# Addon-mapleCUx_Raspi-3V3-UART-CC2530-V01.net
KiCad netlist of a schematic drawn in EAGLE
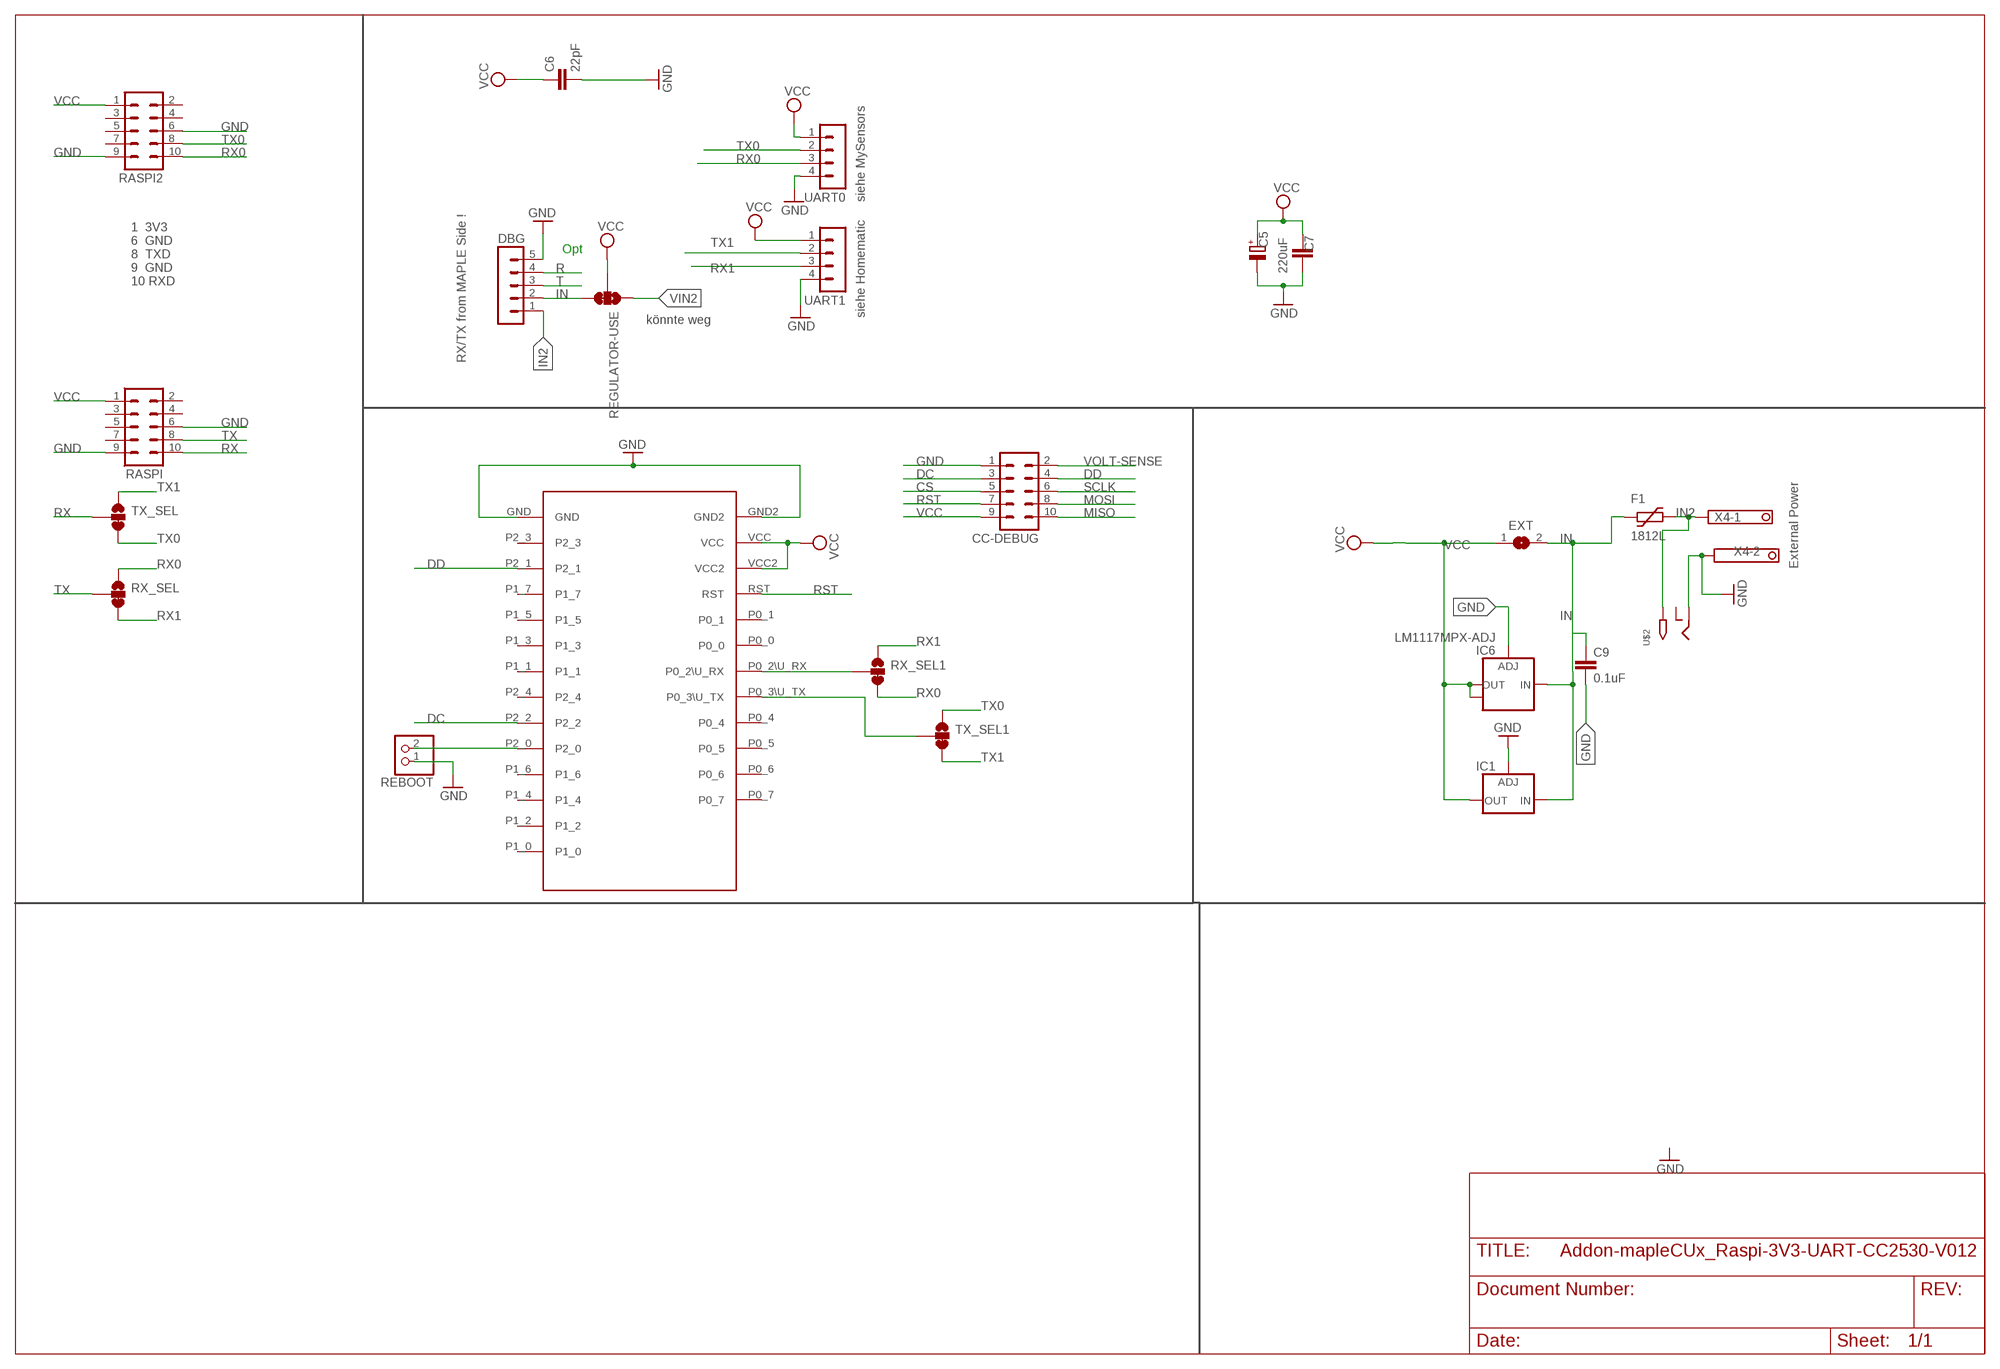
[diagram p0: schematic, sheet 1]

(export (version "E")
  (design (tool "Eeschema 10.0.6"))
  (components
    (comp (ref "C5")
      (value "220uF")
      (footprint "eagle-import:E5-8,5")
      (libsource (lib "eagle-import") (part "CPOL-EUE5-8.5"))
    )
    (comp (ref "C6")
      (value "22pF")
      (footprint "eagle-import:C0805")
      (libsource (lib "eagle-import") (part "C-EUC0805"))
    )
    (comp (ref "C7")
      (value "C-EUC1812")
      (footprint "eagle-import:C1812")
      (libsource (lib "eagle-import") (part "C-EUC1812"))
    )
    (comp (ref "C9")
      (value "0.1uF")
      (footprint "eagle-import:C1206")
      (libsource (lib "eagle-import") (part "C-EUC1206"))
    )
    (comp (ref "CC-DEBUG")
      (value "MA05-2")
      (footprint "eagle-import:MA05-2")
      (libsource (lib "eagle-import") (part "MA05-2"))
    )
    (comp (ref "DBG")
      (value "MA05-1")
      (footprint "eagle-import:MA05-1")
      (libsource (lib "eagle-import") (part "MA05-1"))
    )
    (comp (ref "EXT") (value "SJ") (footprint "eagle-import:SJ") (libsource (lib "eagle-import") (part "SJ")))
    (comp (ref "F1")
      (value "1812L")
      (footprint "eagle-import:1812L")
      (libsource (lib "eagle-import") (part "1812L"))
    )
    (comp (ref "IC1")
      (value "LD117ADT50TR")
      (footprint "eagle-import:DPACK")
      (libsource (lib "eagle-import") (part "LD117A?DT50TR"))
    )
    (comp (ref "IC6")
      (value "LM1117MPX-ADJ")
      (footprint "eagle-import:SOT223")
      (libsource (lib "eagle-import") (part "LM1117MPX-ADJ"))
    )
    (comp (ref "RASPI")
      (value "MA05-2")
      (footprint "eagle-import:MA05-2")
      (libsource (lib "eagle-import") (part "MA05-2"))
    )
    (comp (ref "RASPI2")
      (value "MA05-2")
      (footprint "eagle-import:MA05-2")
      (libsource (lib "eagle-import") (part "MA05-2"))
    )
    (comp (ref "REBOOT")
      (value "PINHD-1X2")
      (footprint "eagle-import:1X02")
      (libsource (lib "eagle-import") (part "PINHD-1X2"))
    )
    (comp (ref "REGULATOR-USE")
      (value "JUMPER-SMT_3_1-NC_TRACE_SILK")
      (footprint "eagle-import:SMT-JUMPER_3_1-NC_TRACE_SILK")
      (libsource (lib "eagle-import") (part "JUMPER-SMT_3_1-NC_TRACE_SILK"))
    )
    (comp (ref "RX_SEL")
      (value "JUMPER-SMT_3_1-NC_TRACE_SILK")
      (footprint "eagle-import:SMT-JUMPER_3_1-NC_TRACE_SILK")
      (libsource (lib "eagle-import") (part "JUMPER-SMT_3_1-NC_TRACE_SILK"))
    )
    (comp (ref "RX_SEL1")
      (value "JUMPER-SMT_3_1-NC_TRACE_SILK")
      (footprint "eagle-import:SMT-JUMPER_3_1-NC_TRACE_SILK")
      (libsource (lib "eagle-import") (part "JUMPER-SMT_3_1-NC_TRACE_SILK"))
    )
    (comp (ref "TX_SEL")
      (value "JUMPER-SMT_3_1-NC_TRACE_SILK")
      (footprint "eagle-import:SMT-JUMPER_3_1-NC_TRACE_SILK")
      (libsource (lib "eagle-import") (part "JUMPER-SMT_3_1-NC_TRACE_SILK"))
    )
    (comp (ref "TX_SEL1")
      (value "JUMPER-SMT_3_1-NC_TRACE_SILK")
      (footprint "eagle-import:SMT-JUMPER_3_1-NC_TRACE_SILK")
      (libsource (lib "eagle-import") (part "JUMPER-SMT_3_1-NC_TRACE_SILK"))
    )
    (comp (ref "U$2")
      (value "2.1MMJACKTHM")
      (footprint "eagle-import:PJ-102A")
      (libsource (lib "eagle-import") (part "2.1MMJACKTHM"))
    )
    (comp (ref "U$3")
      (value "CC2530_MODULE")
      (footprint "eagle-import:CC2530_DIL")
      (libsource (lib "eagle-import") (part "CC2530_MODULE"))
    )
    (comp (ref "UART0")
      (value "MA04-1")
      (footprint "eagle-import:MA04-1")
      (libsource (lib "eagle-import") (part "MA04-1"))
    )
    (comp (ref "UART1")
      (value "MA04-1")
      (footprint "eagle-import:MA04-1")
      (libsource (lib "eagle-import") (part "MA04-1"))
    )
    (comp (ref "X4")
      (value "1751248")
      (footprint "eagle-import:1751248")
      (libsource (lib "eagle-import") (part "1751248"))
    )
  )
  (nets
    (net (code "1") (name "/CS") (class "Default")
      (node (ref "CC-DEBUG") (pin "5") (pinfunction "5_5") (pintype "passive"))
    )
    (net (code "2") (name "/DC") (class "Default")
      (node (ref "CC-DEBUG") (pin "3") (pinfunction "3_3") (pintype "passive"))
      (node (ref "U$3") (pin "P2_2") (pinfunction "P2_2_P2_2") (pintype "bidirectional"))
    )
    (net (code "3") (name "/DD") (class "Default")
      (node (ref "CC-DEBUG") (pin "4") (pinfunction "4_4") (pintype "passive"))
      (node (ref "U$3") (pin "P2_1") (pinfunction "P2_1_P2_1") (pintype "bidirectional"))
    )
    (net (code "4") (name "/IN") (class "Default")
      (node (ref "C9") (pin "1") (pinfunction "1_1") (pintype "passive"))
      (node (ref "DBG") (pin "2") (pinfunction "2_2") (pintype "passive"))
      (node (ref "EXT") (pin "2") (pinfunction "2_2") (pintype "passive"))
      (node (ref "F1") (pin "P$1") (pinfunction "1_P$1") (pintype "passive"))
      (node (ref "IC1") (pin "3") (pinfunction "IN_3") (pintype "input"))
      (node (ref "IC6") (pin "3") (pinfunction "IN_3") (pintype "input"))
      (node (ref "REGULATOR-USE") (pin "3") (pinfunction "3_3") (pintype "passive"))
    )
    (net (code "5") (name "/MISO") (class "Default")
      (node (ref "CC-DEBUG") (pin "10") (pinfunction "10_10") (pintype "passive"))
    )
    (net (code "6") (name "/MOSI") (class "Default")
      (node (ref "CC-DEBUG") (pin "8") (pinfunction "8_8") (pintype "passive"))
    )
    (net (code "7") (name "/R") (class "Default")
      (node (ref "DBG") (pin "4") (pinfunction "4_4") (pintype "passive"))
    )
    (net (code "8") (name "/RST") (class "Default")
      (node (ref "CC-DEBUG") (pin "7") (pinfunction "7_7") (pintype "passive"))
      (node (ref "U$3") (pin "RST") (pinfunction "RST_RST") (pintype "bidirectional"))
    )
    (net (code "9") (name "/RX") (class "Default")
      (node (ref "RASPI") (pin "10") (pinfunction "10_10") (pintype "passive"))
      (node (ref "TX_SEL") (pin "2") (pinfunction "2_2") (pintype "passive"))
    )
    (net (code "10") (name "/RX0") (class "Default")
      (node (ref "RASPI2") (pin "10") (pinfunction "10_10") (pintype "passive"))
      (node (ref "RX_SEL") (pin "1") (pinfunction "1_1") (pintype "passive"))
      (node (ref "RX_SEL1") (pin "3") (pinfunction "3_3") (pintype "passive"))
      (node (ref "UART0") (pin "3") (pinfunction "3_3") (pintype "passive"))
    )
    (net (code "11") (name "/RX1") (class "Default")
      (node (ref "RX_SEL") (pin "3") (pinfunction "3_3") (pintype "passive"))
      (node (ref "RX_SEL1") (pin "1") (pinfunction "1_1") (pintype "passive"))
      (node (ref "UART1") (pin "3") (pinfunction "3_3") (pintype "passive"))
    )
    (net (code "12") (name "/SCLK") (class "Default")
      (node (ref "CC-DEBUG") (pin "6") (pinfunction "6_6") (pintype "passive"))
    )
    (net (code "13") (name "/T") (class "Default")
      (node (ref "DBG") (pin "3") (pinfunction "3_3") (pintype "passive"))
    )
    (net (code "14") (name "/TX") (class "Default")
      (node (ref "RASPI") (pin "8") (pinfunction "8_8") (pintype "passive"))
      (node (ref "RX_SEL") (pin "2") (pinfunction "2_2") (pintype "passive"))
    )
    (net (code "15") (name "/TX0") (class "Default")
      (node (ref "RASPI2") (pin "8") (pinfunction "8_8") (pintype "passive"))
      (node (ref "TX_SEL") (pin "3") (pinfunction "3_3") (pintype "passive"))
      (node (ref "TX_SEL1") (pin "1") (pinfunction "1_1") (pintype "passive"))
      (node (ref "UART0") (pin "2") (pinfunction "2_2") (pintype "passive"))
    )
    (net (code "16") (name "/TX1") (class "Default")
      (node (ref "TX_SEL") (pin "1") (pinfunction "1_1") (pintype "passive"))
      (node (ref "TX_SEL1") (pin "3") (pinfunction "3_3") (pintype "passive"))
      (node (ref "UART1") (pin "2") (pinfunction "2_2") (pintype "passive"))
    )
    (net (code "17") (name "/VOLT-SENSE") (class "Default")
      (node (ref "CC-DEBUG") (pin "2") (pinfunction "2_2") (pintype "passive"))
    )
    (net (code "18") (name "GND") (class "Default")
      (node (ref "C5") (pin "-") (pinfunction "-_-") (pintype "passive"))
      (node (ref "C6") (pin "2") (pinfunction "2_2") (pintype "passive"))
      (node (ref "C7") (pin "1") (pinfunction "1_1") (pintype "passive"))
      (node (ref "C9") (pin "2") (pinfunction "2_2") (pintype "passive"))
      (node (ref "CC-DEBUG") (pin "1") (pinfunction "1_1") (pintype "passive"))
      (node (ref "DBG") (pin "5") (pinfunction "5_5") (pintype "passive"))
      (node (ref "IC1") (pin "1") (pinfunction "ADJ_1") (pintype "input"))
      (node (ref "IC6") (pin "1") (pinfunction "ADJ_1") (pintype "input"))
      (node (ref "RASPI") (pin "6") (pinfunction "6_6") (pintype "passive"))
      (node (ref "RASPI") (pin "9") (pinfunction "9_9") (pintype "passive"))
      (node (ref "RASPI2") (pin "6") (pinfunction "6_6") (pintype "passive"))
      (node (ref "RASPI2") (pin "9") (pinfunction "9_9") (pintype "passive"))
      (node (ref "REBOOT") (pin "1") (pinfunction "1_1") (pintype "passive"))
      (node (ref "U$2") (pin "RING") (pinfunction "RING_RING") (pintype "bidirectional"))
      (node (ref "U$3") (pin "GND") (pinfunction "GND_GND") (pintype "bidirectional"))
      (node (ref "U$3") (pin "GND2") (pinfunction "GND2_GND2") (pintype "bidirectional"))
      (node (ref "UART0") (pin "4") (pinfunction "4_4") (pintype "passive"))
      (node (ref "UART1") (pin "4") (pinfunction "4_4") (pintype "passive"))
      (node (ref "X4") (pin "2") (pinfunction "K_2") (pintype "passive"))
    )
    (net (code "19") (name "IN2") (class "Default")
      (node (ref "DBG") (pin "1") (pinfunction "1_1") (pintype "passive"))
      (node (ref "F1") (pin "P$2") (pinfunction "2_P$2") (pintype "passive"))
      (node (ref "U$2") (pin "TIP") (pinfunction "TIP_TIP") (pintype "bidirectional"))
      (node (ref "X4") (pin "1") (pinfunction "K_1") (pintype "passive"))
    )
    (net (code "20") (name "Net-(REBOOT-Pad2)") (class "Default")
      (node (ref "REBOOT") (pin "2") (pinfunction "2_2") (pintype "passive"))
      (node (ref "U$3") (pin "P2_0") (pinfunction "P2_0_P2_0") (pintype "bidirectional"))
    )
    (net (code "21") (name "Net-(RX_SEL1-Pad2)") (class "Default")
      (node (ref "RX_SEL1") (pin "2") (pinfunction "2_2") (pintype "passive"))
      (node (ref "U$3") (pin "P0_2\\U_RX") (pinfunction "P0_2\\U_RX_P0_2\\U_RX") (pintype "bidirectional"))
    )
    (net (code "22") (name "Net-(TX_SEL1-Pad2)") (class "Default")
      (node (ref "TX_SEL1") (pin "2") (pinfunction "2_2") (pintype "passive"))
      (node (ref "U$3") (pin "P0_3\\U_TX") (pinfunction "P0_3\\U_TX_P0_3\\U_TX") (pintype "bidirectional"))
    )
    (net (code "23") (name "VCC") (class "Default")
      (node (ref "C5") (pin "+") (pinfunction "+_+") (pintype "passive"))
      (node (ref "C6") (pin "1") (pinfunction "1_1") (pintype "passive"))
      (node (ref "C7") (pin "2") (pinfunction "2_2") (pintype "passive"))
      (node (ref "CC-DEBUG") (pin "9") (pinfunction "9_9") (pintype "passive"))
      (node (ref "EXT") (pin "1") (pinfunction "1_1") (pintype "passive"))
      (node (ref "IC1") (pin "4") (pinfunction "OUT_4") (pintype "passive"))
      (node (ref "IC6") (pin "2") (pinfunction "OUT_2") (pintype "passive"))
      (node (ref "IC6") (pin "TAB") (pinfunction "OUT1_TAB") (pintype "passive"))
      (node (ref "RASPI") (pin "1") (pinfunction "1_1") (pintype "passive"))
      (node (ref "RASPI2") (pin "1") (pinfunction "1_1") (pintype "passive"))
      (node (ref "REGULATOR-USE") (pin "2") (pinfunction "2_2") (pintype "passive"))
      (node (ref "U$3") (pin "VCC") (pinfunction "VCC_VCC") (pintype "bidirectional"))
      (node (ref "U$3") (pin "VCC2") (pinfunction "VCC2_VCC2") (pintype "bidirectional"))
      (node (ref "UART0") (pin "1") (pinfunction "1_1") (pintype "passive"))
      (node (ref "UART1") (pin "1") (pinfunction "1_1") (pintype "passive"))
    )
    (net (code "24") (name "VIN2") (class "Default")
      (node (ref "REGULATOR-USE") (pin "1") (pinfunction "1_1") (pintype "passive"))
    )
    (net (code "25") (name "unconnected-(RASPI-Pad2)") (class "Default")
      (node (ref "RASPI") (pin "2") (pinfunction "2_2") (pintype "passive"))
    )
    (net (code "26") (name "unconnected-(RASPI-Pad3)") (class "Default")
      (node (ref "RASPI") (pin "3") (pinfunction "3_3") (pintype "passive"))
    )
    (net (code "27") (name "unconnected-(RASPI-Pad4)") (class "Default")
      (node (ref "RASPI") (pin "4") (pinfunction "4_4") (pintype "passive"))
    )
    (net (code "28") (name "unconnected-(RASPI-Pad5)") (class "Default")
      (node (ref "RASPI") (pin "5") (pinfunction "5_5") (pintype "passive"))
    )
    (net (code "29") (name "unconnected-(RASPI-Pad7)") (class "Default")
      (node (ref "RASPI") (pin "7") (pinfunction "7_7") (pintype "passive"))
    )
    (net (code "30") (name "unconnected-(RASPI2-Pad2)") (class "Default")
      (node (ref "RASPI2") (pin "2") (pinfunction "2_2") (pintype "passive"))
    )
    (net (code "31") (name "unconnected-(RASPI2-Pad3)") (class "Default")
      (node (ref "RASPI2") (pin "3") (pinfunction "3_3") (pintype "passive"))
    )
    (net (code "32") (name "unconnected-(RASPI2-Pad4)") (class "Default")
      (node (ref "RASPI2") (pin "4") (pinfunction "4_4") (pintype "passive"))
    )
    (net (code "33") (name "unconnected-(RASPI2-Pad5)") (class "Default")
      (node (ref "RASPI2") (pin "5") (pinfunction "5_5") (pintype "passive"))
    )
    (net (code "34") (name "unconnected-(RASPI2-Pad7)") (class "Default")
      (node (ref "RASPI2") (pin "7") (pinfunction "7_7") (pintype "passive"))
    )
    (net (code "35") (name "unconnected-(U$2-PadRING_SW)") (class "Default")
      (node (ref "U$2") (pin "RING_SW") (pinfunction "RING_SW_RING_SW") (pintype "bidirectional"))
    )
    (net (code "36") (name "unconnected-(U$3-PadP0_0)") (class "Default")
      (node (ref "U$3") (pin "P0_0") (pinfunction "P0_0_P0_0") (pintype "bidirectional"))
    )
    (net (code "37") (name "unconnected-(U$3-PadP0_1)") (class "Default")
      (node (ref "U$3") (pin "P0_1") (pinfunction "P0_1_P0_1") (pintype "bidirectional"))
    )
    (net (code "38") (name "unconnected-(U$3-PadP0_4)") (class "Default")
      (node (ref "U$3") (pin "P0_4") (pinfunction "P0_4_P0_4") (pintype "bidirectional"))
    )
    (net (code "39") (name "unconnected-(U$3-PadP0_5)") (class "Default")
      (node (ref "U$3") (pin "P0_5") (pinfunction "P0_5_P0_5") (pintype "bidirectional"))
    )
    (net (code "40") (name "unconnected-(U$3-PadP0_6)") (class "Default")
      (node (ref "U$3") (pin "P0_6") (pinfunction "P0_6_P0_6") (pintype "bidirectional"))
    )
    (net (code "41") (name "unconnected-(U$3-PadP0_7)") (class "Default")
      (node (ref "U$3") (pin "P0_7") (pinfunction "P0_7_P0_7") (pintype "bidirectional"))
    )
    (net (code "42") (name "unconnected-(U$3-PadP1_0)") (class "Default")
      (node (ref "U$3") (pin "P1_0") (pinfunction "P1_0_P1_0") (pintype "bidirectional"))
    )
    (net (code "43") (name "unconnected-(U$3-PadP1_1)") (class "Default")
      (node (ref "U$3") (pin "P1_1") (pinfunction "P1_1_P1_1") (pintype "bidirectional"))
    )
    (net (code "44") (name "unconnected-(U$3-PadP1_2)") (class "Default")
      (node (ref "U$3") (pin "P1_2") (pinfunction "P1_2_P1_2") (pintype "bidirectional"))
    )
    (net (code "45") (name "unconnected-(U$3-PadP1_3)") (class "Default")
      (node (ref "U$3") (pin "P1_3") (pinfunction "P1_3_P1_3") (pintype "bidirectional"))
    )
    (net (code "46") (name "unconnected-(U$3-PadP1_4)") (class "Default")
      (node (ref "U$3") (pin "P1_4") (pinfunction "P1_4_P1_4") (pintype "bidirectional"))
    )
    (net (code "47") (name "unconnected-(U$3-PadP1_5)") (class "Default")
      (node (ref "U$3") (pin "P1_5") (pinfunction "P1_5_P1_5") (pintype "bidirectional"))
    )
    (net (code "48") (name "unconnected-(U$3-PadP1_6)") (class "Default")
      (node (ref "U$3") (pin "P1_6") (pinfunction "P1_6_P1_6") (pintype "bidirectional"))
    )
    (net (code "49") (name "unconnected-(U$3-PadP1_7)") (class "Default")
      (node (ref "U$3") (pin "P1_7") (pinfunction "P1_7_P1_7") (pintype "bidirectional"))
    )
    (net (code "50") (name "unconnected-(U$3-PadP2_3)") (class "Default")
      (node (ref "U$3") (pin "P2_3") (pinfunction "P2_3_P2_3") (pintype "bidirectional"))
    )
    (net (code "51") (name "unconnected-(U$3-PadP2_4)") (class "Default")
      (node (ref "U$3") (pin "P2_4") (pinfunction "P2_4_P2_4") (pintype "bidirectional"))
    )
  )
)
